# Motor_Control.net
KiCad netlist of a schematic drawn in Altium Designer
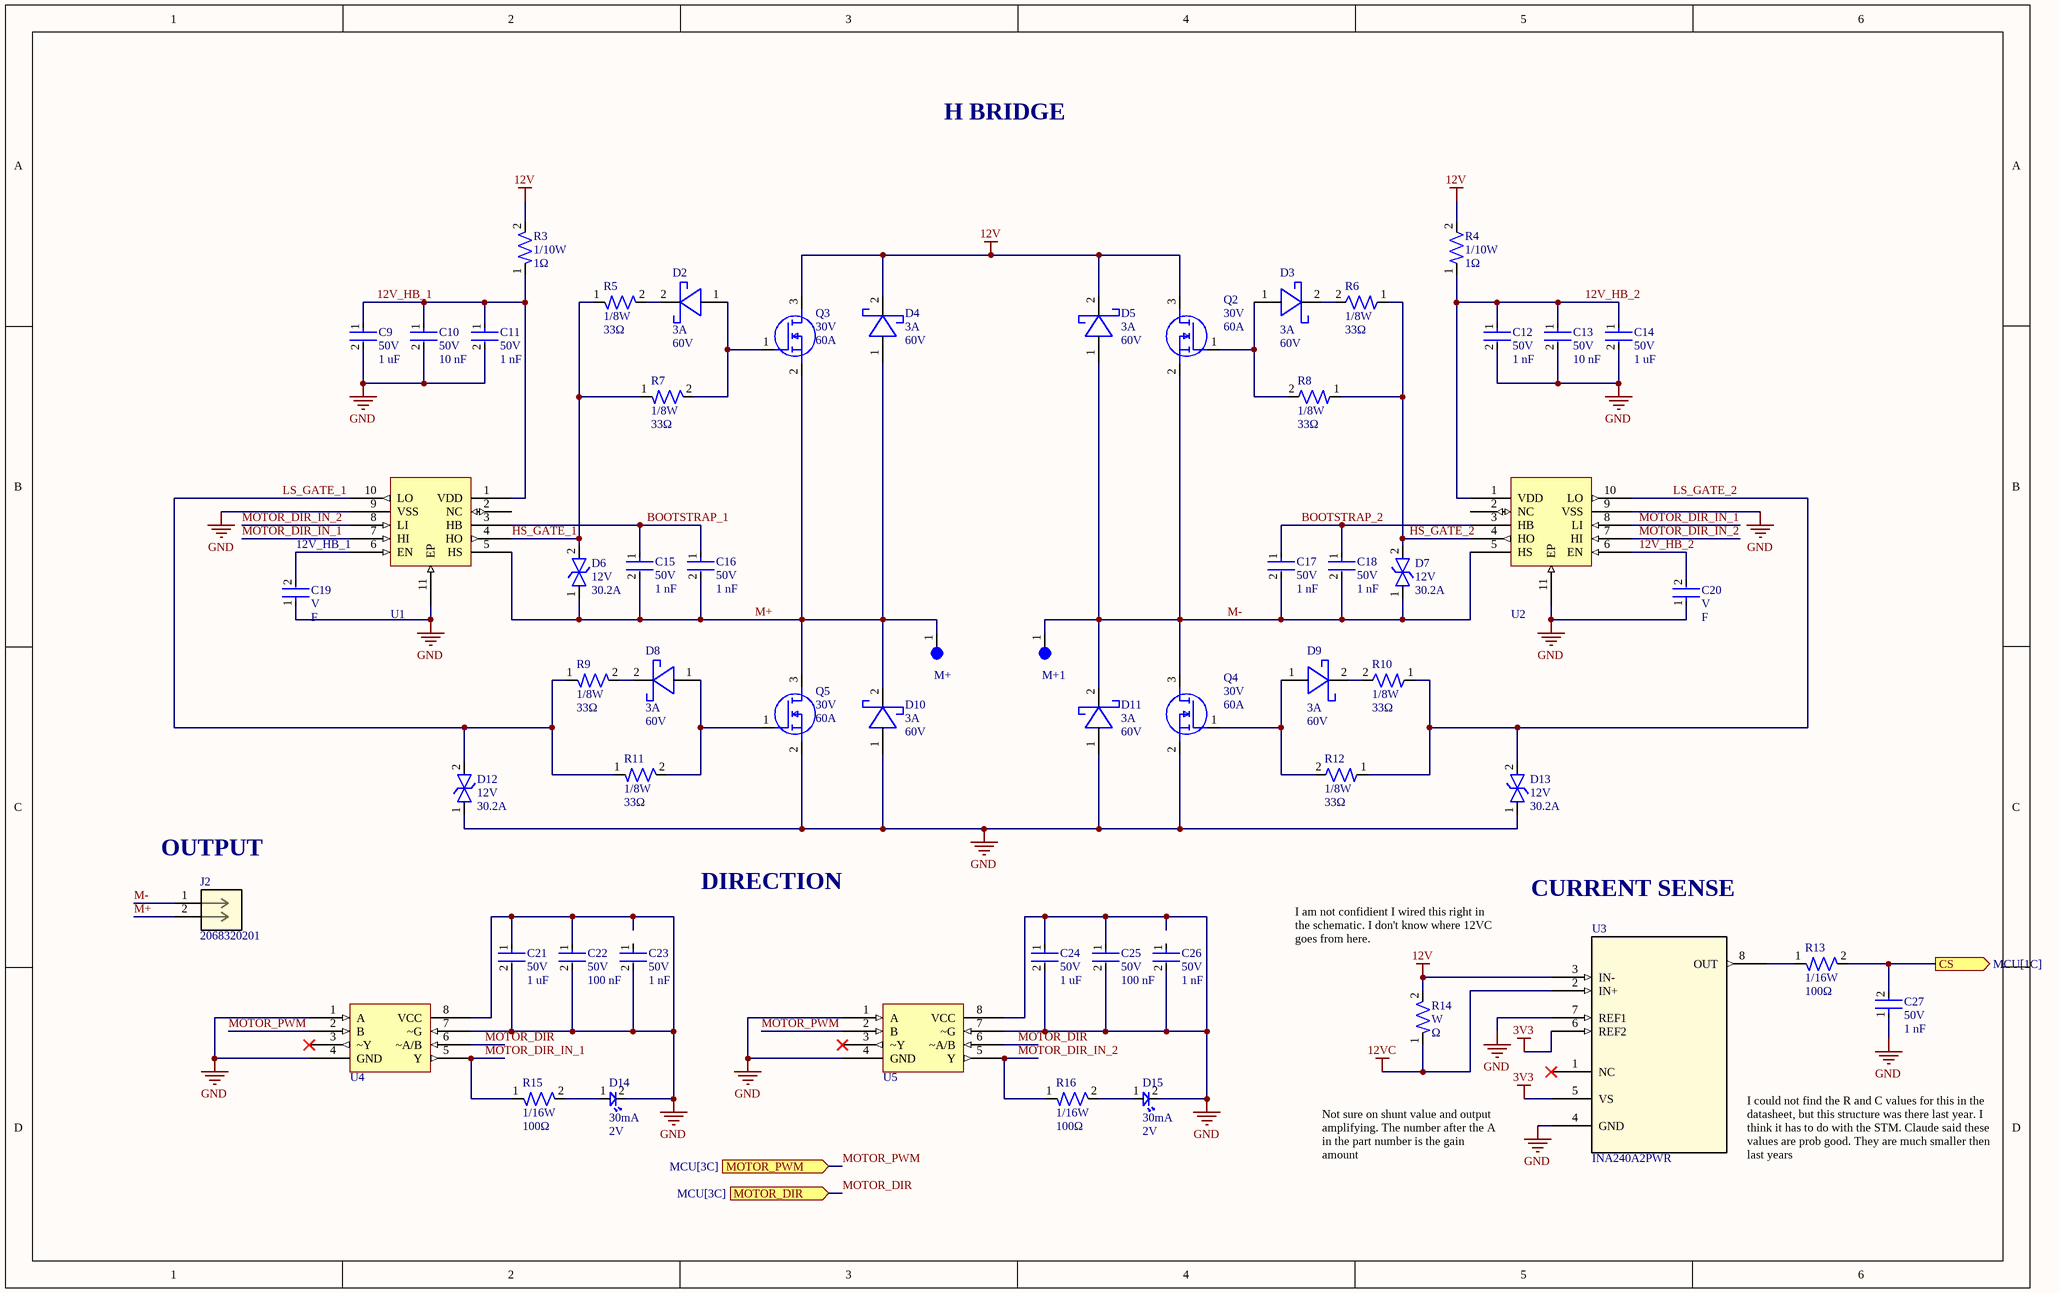
[diagram p0: Motor Control.SchDoc]

(export (version "E")
  (design (tool "Eeschema 10.0.6"))
  (components
    (comp (ref "C9")
      (value "CAP 0805")
      (footprint "CAP-0805")
      (fields (field (name "VOLTAGE RATING") "50V") (field (name "CAPACITANCE") "1 uF"))
      (libsource (lib "EHW_27") (part "CAP 0805"))
    )
    (comp (ref "C10")
      (value "CAP 0805")
      (footprint "CAP-0805")
      (fields (field (name "VOLTAGE RATING") "50V") (field (name "CAPACITANCE") "10 nF"))
      (libsource (lib "EHW_27") (part "CAP 0805"))
    )
    (comp (ref "C11")
      (value "CAP 0805")
      (footprint "CAP-0805")
      (fields (field (name "VOLTAGE RATING") "50V") (field (name "CAPACITANCE") "1 nF"))
      (libsource (lib "EHW_27") (part "CAP 0805"))
    )
    (comp (ref "C12")
      (value "CAP 0805")
      (footprint "CAP-0805")
      (fields (field (name "VOLTAGE RATING") "50V") (field (name "CAPACITANCE") "1 nF"))
      (libsource (lib "EHW_27") (part "CAP 0805"))
    )
    (comp (ref "C13")
      (value "CAP 0805")
      (footprint "CAP-0805")
      (fields (field (name "VOLTAGE RATING") "50V") (field (name "CAPACITANCE") "10 nF"))
      (libsource (lib "EHW_27") (part "CAP 0805"))
    )
    (comp (ref "C14")
      (value "CAP 0805")
      (footprint "CAP-0805")
      (fields (field (name "VOLTAGE RATING") "50V") (field (name "CAPACITANCE") "1 uF"))
      (libsource (lib "EHW_27") (part "CAP 0805"))
    )
    (comp (ref "C15")
      (value "CAP 0805")
      (footprint "CAP-0805")
      (fields (field (name "VOLTAGE RATING") "50V") (field (name "CAPACITANCE") "1 nF"))
      (libsource (lib "EHW_27") (part "CAP 0805"))
    )
    (comp (ref "C16")
      (value "CAP 0805")
      (footprint "CAP-0805")
      (fields (field (name "VOLTAGE RATING") "50V") (field (name "CAPACITANCE") "1 nF"))
      (libsource (lib "EHW_27") (part "CAP 0805"))
    )
    (comp (ref "C17")
      (value "CAP 0805")
      (footprint "CAP-0805")
      (fields (field (name "VOLTAGE RATING") "50V") (field (name "CAPACITANCE") "1 nF"))
      (libsource (lib "EHW_27") (part "CAP 0805"))
    )
    (comp (ref "C18")
      (value "CAP 0805")
      (footprint "CAP-0805")
      (fields (field (name "VOLTAGE RATING") "50V") (field (name "CAPACITANCE") "1 nF"))
      (libsource (lib "EHW_27") (part "CAP 0805"))
    )
    (comp (ref "C19")
      (value "CAP 0603")
      (footprint "CAP-0603")
      (fields (field (name "VOLTAGE RATING") "V") (field (name "CAPACITANCE") "F"))
      (libsource (lib "EHW_27") (part "CAP 0603"))
    )
    (comp (ref "C20")
      (value "CAP 0603")
      (footprint "CAP-0603")
      (fields (field (name "VOLTAGE RATING") "V") (field (name "CAPACITANCE") "F"))
      (libsource (lib "EHW_27") (part "CAP 0603"))
    )
    (comp (ref "C21")
      (value "CAP 0805")
      (footprint "CAP-0805")
      (fields (field (name "VOLTAGE RATING") "50V") (field (name "CAPACITANCE") "1 uF"))
      (libsource (lib "EHW_27") (part "CAP 0805"))
    )
    (comp (ref "C22")
      (value "CAP 0805")
      (footprint "CAP-0805")
      (fields (field (name "VOLTAGE RATING") "50V") (field (name "CAPACITANCE") "100 nF"))
      (libsource (lib "EHW_27") (part "CAP 0805"))
    )
    (comp (ref "C23")
      (value "CAP 0805")
      (footprint "CAP-0805")
      (fields (field (name "VOLTAGE RATING") "50V") (field (name "CAPACITANCE") "1 nF"))
      (libsource (lib "EHW_27") (part "CAP 0805"))
    )
    (comp (ref "C24")
      (value "CAP 0805")
      (footprint "CAP-0805")
      (fields (field (name "VOLTAGE RATING") "50V") (field (name "CAPACITANCE") "1 uF"))
      (libsource (lib "EHW_27") (part "CAP 0805"))
    )
    (comp (ref "C25")
      (value "CAP 0805")
      (footprint "CAP-0805")
      (fields (field (name "VOLTAGE RATING") "50V") (field (name "CAPACITANCE") "100 nF"))
      (libsource (lib "EHW_27") (part "CAP 0805"))
    )
    (comp (ref "C26")
      (value "CAP 0805")
      (footprint "CAP-0805")
      (fields (field (name "VOLTAGE RATING") "50V") (field (name "CAPACITANCE") "1 nF"))
      (libsource (lib "EHW_27") (part "CAP 0805"))
    )
    (comp (ref "C27")
      (value "CAP 0805")
      (footprint "CAP-0805")
      (fields (field (name "VOLTAGE RATING") "50V") (field (name "CAPACITANCE") "1 nF"))
      (libsource (lib "EHW_27") (part "CAP 0805"))
    )
    (comp (ref "D2")
      (value "PMEG6030EP,115")
      (footprint "DIO-SOD128")
      (description "DIODE SCHOTTKY 60V 3A SOD128")
      (fields (field (name "CURRENT RATING") "3A") (field (name "REVERSE VOLTAGE") "60V"))
      (libsource (lib "EHW_27") (part "DIO-SCHOTTKY-0003"))
    )
    (comp (ref "D3")
      (value "PMEG6030EP,115")
      (footprint "DIO-SOD128")
      (description "DIODE SCHOTTKY 60V 3A SOD128")
      (fields (field (name "CURRENT RATING") "3A") (field (name "REVERSE VOLTAGE") "60V"))
      (libsource (lib "EHW_27") (part "DIO-SCHOTTKY-0003"))
    )
    (comp (ref "D4")
      (value "PMEG6030EP,115")
      (footprint "DIO-SOD128")
      (description "DIODE SCHOTTKY 60V 3A SOD128")
      (fields (field (name "CURRENT RATING") "3A") (field (name "REVERSE VOLTAGE") "60V"))
      (libsource (lib "EHW_27") (part "DIO-SCHOTTKY-0003"))
    )
    (comp (ref "D5")
      (value "PMEG6030EP,115")
      (footprint "DIO-SOD128")
      (description "DIODE SCHOTTKY 60V 3A SOD128")
      (fields (field (name "CURRENT RATING") "3A") (field (name "REVERSE VOLTAGE") "60V"))
      (libsource (lib "EHW_27") (part "DIO-SCHOTTKY-0003"))
    )
    (comp (ref "D6")
      (value "SMBJ40CA")
      (footprint "DO-214AA (SMBJ)")
      (description "TVS DIODE 40VWM 64.5VC DO214AA")
      (fields (field (name "VOLTAGE RATING") "12V") (field (name "CURRENT RATING") "30.2A"))
      (libsource (lib "EHW_27") (part "DIO-TVS-0001"))
    )
    (comp (ref "D7")
      (value "SMBJ40CA")
      (footprint "DO-214AA (SMBJ)")
      (description "TVS DIODE 40VWM 64.5VC DO214AA")
      (fields (field (name "VOLTAGE RATING") "12V") (field (name "CURRENT RATING") "30.2A"))
      (libsource (lib "EHW_27") (part "DIO-TVS-0001"))
    )
    (comp (ref "D8")
      (value "PMEG6030EP,115")
      (footprint "DIO-SOD128")
      (description "DIODE SCHOTTKY 60V 3A SOD128")
      (fields (field (name "CURRENT RATING") "3A") (field (name "REVERSE VOLTAGE") "60V"))
      (libsource (lib "EHW_27") (part "DIO-SCHOTTKY-0003"))
    )
    (comp (ref "D9")
      (value "PMEG6030EP,115")
      (footprint "DIO-SOD128")
      (description "DIODE SCHOTTKY 60V 3A SOD128")
      (fields (field (name "CURRENT RATING") "3A") (field (name "REVERSE VOLTAGE") "60V"))
      (libsource (lib "EHW_27") (part "DIO-SCHOTTKY-0003"))
    )
    (comp (ref "D10")
      (value "PMEG6030EP,115")
      (footprint "DIO-SOD128")
      (description "DIODE SCHOTTKY 60V 3A SOD128")
      (fields (field (name "CURRENT RATING") "3A") (field (name "REVERSE VOLTAGE") "60V"))
      (libsource (lib "EHW_27") (part "DIO-SCHOTTKY-0003"))
    )
    (comp (ref "D11")
      (value "PMEG6030EP,115")
      (footprint "DIO-SOD128")
      (description "DIODE SCHOTTKY 60V 3A SOD128")
      (fields (field (name "CURRENT RATING") "3A") (field (name "REVERSE VOLTAGE") "60V"))
      (libsource (lib "EHW_27") (part "DIO-SCHOTTKY-0003"))
    )
    (comp (ref "D12")
      (value "SMBJ40CA")
      (footprint "DO-214AA (SMBJ)")
      (description "TVS DIODE 40VWM 64.5VC DO214AA")
      (fields (field (name "VOLTAGE RATING") "12V") (field (name "CURRENT RATING") "30.2A"))
      (libsource (lib "EHW_27") (part "DIO-TVS-0001"))
    )
    (comp (ref "D13")
      (value "SMBJ40CA")
      (footprint "DO-214AA (SMBJ)")
      (description "TVS DIODE 40VWM 64.5VC DO214AA")
      (fields (field (name "VOLTAGE RATING") "12V") (field (name "CURRENT RATING") "30.2A"))
      (libsource (lib "EHW_27") (part "DIO-TVS-0001"))
    )
    (comp (ref "D14")
      (value "BL-HKC36G-AV-TRB")
      (footprint "LED-0603")
      (description "LED YELLOW CLEAR 0603 SMD")
      (fields (field (name "FORWARD CURRENT") "30mA") (field (name "FORWARD VOLTAGE") "2V"))
      (libsource (lib "EHW_27") (part "LED-0001"))
    )
    (comp (ref "D15")
      (value "BL-HKC36G-AV-TRB")
      (footprint "LED-0603")
      (description "LED YELLOW CLEAR 0603 SMD")
      (fields (field (name "FORWARD CURRENT") "30mA") (field (name "FORWARD VOLTAGE") "2V"))
      (libsource (lib "EHW_27") (part "LED-0001"))
    )
    (comp (ref "J2")
      (value "2068320201")
      (footprint "CONN_2068320000-SD_02_MOL")
      (fields (field (name "COPYRIGHT") "Copyright (C) 2025 Ultra Librarian. All rights reserved."))
      (libsource (lib "EHW_27") (part "CONN MF+ 2 PIN VERT"))
    )
    (comp (ref "M+")
      (value "5003")
      (footprint "TEST-POINT-0001")
      (description "Oranange PC Test Point, Miniature Phoisphor Bronze Silver Plating Through Hole Mounting Type")
      (libsource (lib "EHW_27") (part "TEST-POINT-0001"))
    )
    (comp (ref "M+1")
      (value "5003")
      (footprint "TEST-POINT-0001")
      (description "Oranange PC Test Point, Miniature Phoisphor Bronze Silver Plating Through Hole Mounting Type")
      (libsource (lib "EHW_27") (part "TEST-POINT-0001"))
    )
    (comp (ref "Q2")
      (value "CSD17575Q3")
      (footprint "IC-8VSONCLIP")
      (description "MOSFET N-CH 30V 60A 8VSON")
      (fields (field (name "VOLTAGE") "30V") (field (name "CONTINUOUS CURRENT") "60A"))
      (libsource (lib "EHW_27") (part "NMOS-26A-0001"))
    )
    (comp (ref "Q3")
      (value "CSD17575Q3")
      (footprint "IC-8VSONCLIP")
      (description "MOSFET N-CH 30V 60A 8VSON")
      (fields (field (name "VOLTAGE") "30V") (field (name "CONTINUOUS CURRENT") "60A"))
      (libsource (lib "EHW_27") (part "NMOS-26A-0001"))
    )
    (comp (ref "Q4")
      (value "CSD17575Q3")
      (footprint "IC-8VSONCLIP")
      (description "MOSFET N-CH 30V 60A 8VSON")
      (fields (field (name "VOLTAGE") "30V") (field (name "CONTINUOUS CURRENT") "60A"))
      (libsource (lib "EHW_27") (part "NMOS-26A-0001"))
    )
    (comp (ref "Q5")
      (value "CSD17575Q3")
      (footprint "IC-8VSONCLIP")
      (description "MOSFET N-CH 30V 60A 8VSON")
      (fields (field (name "VOLTAGE") "30V") (field (name "CONTINUOUS CURRENT") "60A"))
      (libsource (lib "EHW_27") (part "NMOS-26A-0001"))
    )
    (comp (ref "R3")
      (value "RES 0805")
      (footprint "RES-0805")
      (fields (field (name "WATTAGE") "1/10W") (field (name "RESISTANCE") "1Ω"))
      (libsource (lib "EHW_27") (part "RES 0805"))
    )
    (comp (ref "R4")
      (value "RES 0805")
      (footprint "RES-0805")
      (fields (field (name "WATTAGE") "1/10W") (field (name "RESISTANCE") "1Ω"))
      (libsource (lib "EHW_27") (part "RES 0805"))
    )
    (comp (ref "R5")
      (value "RES 0805")
      (footprint "RES-0805")
      (fields (field (name "WATTAGE") "1/8W") (field (name "RESISTANCE") "33Ω"))
      (libsource (lib "EHW_27") (part "RES 0805"))
    )
    (comp (ref "R6")
      (value "RES 0805")
      (footprint "RES-0805")
      (fields (field (name "WATTAGE") "1/8W") (field (name "RESISTANCE") "33Ω"))
      (libsource (lib "EHW_27") (part "RES 0805"))
    )
    (comp (ref "R7")
      (value "RES 0805")
      (footprint "RES-0805")
      (fields (field (name "WATTAGE") "1/8W") (field (name "RESISTANCE") "33Ω"))
      (libsource (lib "EHW_27") (part "RES 0805"))
    )
    (comp (ref "R8")
      (value "RES 0805")
      (footprint "RES-0805")
      (fields (field (name "WATTAGE") "1/8W") (field (name "RESISTANCE") "33Ω"))
      (libsource (lib "EHW_27") (part "RES 0805"))
    )
    (comp (ref "R9")
      (value "RES 0805")
      (footprint "RES-0805")
      (fields (field (name "WATTAGE") "1/8W") (field (name "RESISTANCE") "33Ω"))
      (libsource (lib "EHW_27") (part "RES 0805"))
    )
    (comp (ref "R10")
      (value "RES 0805")
      (footprint "RES-0805")
      (fields (field (name "WATTAGE") "1/8W") (field (name "RESISTANCE") "33Ω"))
      (libsource (lib "EHW_27") (part "RES 0805"))
    )
    (comp (ref "R11")
      (value "RES 0805")
      (footprint "RES-0805")
      (fields (field (name "WATTAGE") "1/8W") (field (name "RESISTANCE") "33Ω"))
      (libsource (lib "EHW_27") (part "RES 0805"))
    )
    (comp (ref "R12")
      (value "RES 0805")
      (footprint "RES-0805")
      (fields (field (name "WATTAGE") "1/8W") (field (name "RESISTANCE") "33Ω"))
      (libsource (lib "EHW_27") (part "RES 0805"))
    )
    (comp (ref "R13")
      (value "RES 0805")
      (footprint "RES-0805")
      (fields (field (name "WATTAGE") "1/16W") (field (name "RESISTANCE") "100Ω"))
      (libsource (lib "EHW_27") (part "RES 0805"))
    )
    (comp (ref "R14")
      (value "RES 2512")
      (footprint "RES-2512")
      (fields (field (name "WATTAGE") "W") (field (name "RESISTANCE") "Ω"))
      (libsource (lib "EHW_27") (part "RES 2512"))
    )
    (comp (ref "R15")
      (value "RES 0805")
      (footprint "RES-0805")
      (fields (field (name "WATTAGE") "1/16W") (field (name "RESISTANCE") "100Ω"))
      (libsource (lib "EHW_27") (part "RES 0805"))
    )
    (comp (ref "R16")
      (value "RES 0805")
      (footprint "RES-0805")
      (fields (field (name "WATTAGE") "1/16W") (field (name "RESISTANCE") "100Ω"))
      (libsource (lib "EHW_27") (part "RES 0805"))
    )
    (comp (ref "U1")
      (value "UCC27282DRCR")
      (footprint "IC-10VSON")
      (description "IC GATE DRVR HALF-BRIDGE 10VSON")
      (libsource (lib "") (part "IC-GTDR-0001_1"))
    )
    (comp (ref "U2")
      (value "UCC27282DRCR")
      (footprint "IC-10VSON")
      (description "IC GATE DRVR HALF-BRIDGE 10VSON")
      (libsource (lib "EHW_27") (part "IC-GTDR-0001"))
    )
    (comp (ref "U3")
      (value "INA240A2PWR")
      (footprint "PW0008A_N_TEX")
      (fields (field (name "COPYRIGHT") "Copyright (C) 2026 Ultra Librarian. All rights reserved."))
      (libsource (lib "EHW_27") (part "INA240A2PWR"))
    )
    (comp (ref "U4")
      (value "SN74LVC2G157DCUR")
      (footprint "IC-8VSSOP")
      (description "Multiplexer 1 x 2:1 8-VSSOP")
      (libsource (lib "EHW_27") (part "IC-MUX-0001"))
    )
    (comp (ref "U5")
      (value "SN74LVC2G157DCUR")
      (footprint "IC-8VSSOP")
      (description "Multiplexer 1 x 2:1 8-VSSOP")
      (libsource (lib "EHW_27") (part "IC-MUX-0001"))
    )
  )
  (nets
    (net (code "1") (name "/12V_HB_1") (class "Default")
      (node (ref "C10") (pin "1") (pinfunction "1_1") (pintype "passive"))
      (node (ref "C11") (pin "1") (pinfunction "1_1") (pintype "passive"))
      (node (ref "C9") (pin "1") (pinfunction "1_1") (pintype "passive"))
      (node (ref "R3") (pin "1") (pinfunction "1_1") (pintype "passive"))
      (node (ref "U1") (pin "1") (pinfunction "VDD_1") (pintype "power_in"))
    )
    (net (code "2") (name "/12V_HB_2") (class "Default")
      (node (ref "C12") (pin "1") (pinfunction "1_1") (pintype "passive"))
      (node (ref "C13") (pin "1") (pinfunction "1_1") (pintype "passive"))
      (node (ref "C14") (pin "1") (pinfunction "1_1") (pintype "passive"))
      (node (ref "C20") (pin "2") (pinfunction "2_2") (pintype "passive"))
      (node (ref "R4") (pin "1") (pinfunction "1_1") (pintype "passive"))
      (node (ref "U2") (pin "1") (pinfunction "VDD_1") (pintype "power_in"))
      (node (ref "U2") (pin "6") (pinfunction "EN_6") (pintype "input"))
    )
    (net (code "3") (name "/BOOTSTRAP_1") (class "Default")
      (node (ref "C15") (pin "1") (pinfunction "1_1") (pintype "passive"))
      (node (ref "C16") (pin "1") (pinfunction "1_1") (pintype "passive"))
      (node (ref "U1") (pin "3") (pinfunction "HB_3") (pintype "power_in"))
    )
    (net (code "4") (name "/BOOTSTRAP_2") (class "Default")
      (node (ref "C17") (pin "1") (pinfunction "1_1") (pintype "passive"))
      (node (ref "C18") (pin "1") (pinfunction "1_1") (pintype "passive"))
      (node (ref "U2") (pin "3") (pinfunction "HB_3") (pintype "power_in"))
    )
    (net (code "5") (name "/CS") (class "Default")
      (node (ref "C27") (pin "2") (pinfunction "2_2") (pintype "passive"))
      (node (ref "R13") (pin "2") (pinfunction "2_2") (pintype "passive"))
    )
    (net (code "6") (name "/HS_GATE_1") (class "Default")
      (node (ref "D6") (pin "2") (pintype "passive"))
      (node (ref "R5") (pin "1") (pinfunction "1_1") (pintype "passive"))
      (node (ref "R7") (pin "1") (pinfunction "1_1") (pintype "passive"))
      (node (ref "U1") (pin "4") (pinfunction "HO_4") (pintype "output"))
    )
    (net (code "7") (name "/HS_GATE_2") (class "Default")
      (node (ref "D7") (pin "2") (pintype "passive"))
      (node (ref "R6") (pin "1") (pinfunction "1_1") (pintype "passive"))
      (node (ref "R8") (pin "1") (pinfunction "1_1") (pintype "passive"))
      (node (ref "U2") (pin "4") (pinfunction "HO_4") (pintype "output"))
    )
    (net (code "8") (name "/LS_GATE_1") (class "Default")
      (node (ref "D12") (pin "2") (pintype "passive"))
      (node (ref "R11") (pin "1") (pinfunction "1_1") (pintype "passive"))
      (node (ref "R9") (pin "1") (pinfunction "1_1") (pintype "passive"))
      (node (ref "U1") (pin "10") (pinfunction "LO_10") (pintype "output"))
    )
    (net (code "9") (name "/LS_GATE_2") (class "Default")
      (node (ref "D13") (pin "2") (pintype "passive"))
      (node (ref "R10") (pin "1") (pinfunction "1_1") (pintype "passive"))
      (node (ref "R12") (pin "1") (pinfunction "1_1") (pintype "passive"))
      (node (ref "U2") (pin "10") (pinfunction "LO_10") (pintype "output"))
    )
    (net (code "10") (name "/M+") (class "Default")
      (node (ref "C15") (pin "2") (pinfunction "2_2") (pintype "passive"))
      (node (ref "C16") (pin "2") (pinfunction "2_2") (pintype "passive"))
      (node (ref "D10") (pin "2") (pinfunction "ANODE_2") (pintype "passive"))
      (node (ref "D4") (pin "1") (pinfunction "CATHODE_1") (pintype "passive"))
      (node (ref "D6") (pin "1") (pintype "passive"))
      (node (ref "J2") (pin "2") (pinfunction "2_2") (pintype "passive"))
      (node (ref "M+") (pin "1") (pinfunction "0_1") (pintype "passive"))
      (node (ref "Q3") (pin "2") (pinfunction "S_2") (pintype "passive"))
      (node (ref "Q5") (pin "3") (pinfunction "D_3") (pintype "passive"))
      (node (ref "U1") (pin "5") (pinfunction "HS_5") (pintype "power_in"))
    )
    (net (code "11") (name "/M-") (class "Default")
      (node (ref "C17") (pin "2") (pinfunction "2_2") (pintype "passive"))
      (node (ref "C18") (pin "2") (pinfunction "2_2") (pintype "passive"))
      (node (ref "D11") (pin "2") (pinfunction "ANODE_2") (pintype "passive"))
      (node (ref "D5") (pin "1") (pinfunction "CATHODE_1") (pintype "passive"))
      (node (ref "D7") (pin "1") (pintype "passive"))
      (node (ref "J2") (pin "1") (pinfunction "1_1") (pintype "passive"))
      (node (ref "M+1") (pin "1") (pinfunction "0_1") (pintype "passive"))
      (node (ref "Q2") (pin "2") (pinfunction "S_2") (pintype "passive"))
      (node (ref "Q4") (pin "3") (pinfunction "D_3") (pintype "passive"))
      (node (ref "U2") (pin "5") (pinfunction "HS_5") (pintype "power_in"))
    )
    (net (code "12") (name "/MOTOR_DIR") (class "Default")
      (node (ref "U4") (pin "6") (pinfunction "~A/B_6") (pintype "input"))
      (node (ref "U5") (pin "6") (pinfunction "~A/B_6") (pintype "input"))
    )
    (net (code "13") (name "/MOTOR_DIR_IN_1") (class "Default")
      (node (ref "R15") (pin "1") (pinfunction "1_1") (pintype "passive"))
      (node (ref "U1") (pin "7") (pinfunction "HI_7") (pintype "input"))
      (node (ref "U2") (pin "8") (pinfunction "LI_8") (pintype "input"))
      (node (ref "U4") (pin "5") (pinfunction "Y_5") (pintype "output"))
    )
    (net (code "14") (name "/MOTOR_DIR_IN_2") (class "Default")
      (node (ref "R16") (pin "1") (pinfunction "1_1") (pintype "passive"))
      (node (ref "U1") (pin "8") (pinfunction "LI_8") (pintype "input"))
      (node (ref "U2") (pin "7") (pinfunction "HI_7") (pintype "input"))
      (node (ref "U5") (pin "5") (pinfunction "Y_5") (pintype "output"))
    )
    (net (code "15") (name "/MOTOR_PWM") (class "Default")
      (node (ref "U4") (pin "2") (pinfunction "B_2") (pintype "input"))
      (node (ref "U5") (pin "2") (pinfunction "B_2") (pintype "input"))
    )
    (net (code "16") (name "3V3") (class "Default")
      (node (ref "U3") (pin "5") (pinfunction "VS_5") (pintype "power_in"))
      (node (ref "U3") (pin "6") (pinfunction "REF2_6") (pintype "input"))
    )
    (net (code "17") (name "12V") (class "Default")
      (node (ref "D4") (pin "2") (pinfunction "ANODE_2") (pintype "passive"))
      (node (ref "D5") (pin "2") (pinfunction "ANODE_2") (pintype "passive"))
      (node (ref "Q2") (pin "3") (pinfunction "D_3") (pintype "passive"))
      (node (ref "Q3") (pin "3") (pinfunction "D_3") (pintype "passive"))
      (node (ref "R14") (pin "2") (pinfunction "2_2") (pintype "passive"))
      (node (ref "R3") (pin "2") (pinfunction "2_2") (pintype "passive"))
      (node (ref "R4") (pin "2") (pinfunction "2_2") (pintype "passive"))
      (node (ref "U3") (pin "3") (pinfunction "IN-_3") (pintype "input"))
    )
    (net (code "18") (name "12VC") (class "Default")
      (node (ref "R14") (pin "1") (pinfunction "1_1") (pintype "passive"))
      (node (ref "U3") (pin "2") (pinfunction "IN+_2") (pintype "input"))
    )
    (net (code "19") (name "GND") (class "Default")
      (node (ref "C10") (pin "2") (pinfunction "2_2") (pintype "passive"))
      (node (ref "C11") (pin "2") (pinfunction "2_2") (pintype "passive"))
      (node (ref "C12") (pin "2") (pinfunction "2_2") (pintype "passive"))
      (node (ref "C13") (pin "2") (pinfunction "2_2") (pintype "passive"))
      (node (ref "C14") (pin "2") (pinfunction "2_2") (pintype "passive"))
      (node (ref "C19") (pin "1") (pinfunction "1_1") (pintype "passive"))
      (node (ref "C20") (pin "1") (pinfunction "1_1") (pintype "passive"))
      (node (ref "C21") (pin "1") (pinfunction "1_1") (pintype "passive"))
      (node (ref "C21") (pin "2") (pinfunction "2_2") (pintype "passive"))
      (node (ref "C22") (pin "1") (pinfunction "1_1") (pintype "passive"))
      (node (ref "C22") (pin "2") (pinfunction "2_2") (pintype "passive"))
      (node (ref "C23") (pin "2") (pinfunction "2_2") (pintype "passive"))
      (node (ref "C24") (pin "1") (pinfunction "1_1") (pintype "passive"))
      (node (ref "C24") (pin "2") (pinfunction "2_2") (pintype "passive"))
      (node (ref "C25") (pin "1") (pinfunction "1_1") (pintype "passive"))
      (node (ref "C25") (pin "2") (pinfunction "2_2") (pintype "passive"))
      (node (ref "C26") (pin "2") (pinfunction "2_2") (pintype "passive"))
      (node (ref "C27") (pin "1") (pinfunction "1_1") (pintype "passive"))
      (node (ref "C9") (pin "2") (pinfunction "2_2") (pintype "passive"))
      (node (ref "D10") (pin "1") (pinfunction "CATHODE_1") (pintype "passive"))
      (node (ref "D11") (pin "1") (pinfunction "CATHODE_1") (pintype "passive"))
      (node (ref "D12") (pin "1") (pintype "passive"))
      (node (ref "D13") (pin "1") (pintype "passive"))
      (node (ref "D14") (pin "2") (pinfunction "2_2") (pintype "passive"))
      (node (ref "D15") (pin "2") (pinfunction "2_2") (pintype "passive"))
      (node (ref "Q4") (pin "2") (pinfunction "S_2") (pintype "passive"))
      (node (ref "Q5") (pin "2") (pinfunction "S_2") (pintype "passive"))
      (node (ref "U1") (pin "11") (pinfunction "EP_11") (pintype "input"))
      (node (ref "U1") (pin "9") (pinfunction "VSS_9") (pintype "power_in"))
      (node (ref "U2") (pin "11") (pinfunction "EP_11") (pintype "input"))
      (node (ref "U2") (pin "9") (pinfunction "VSS_9") (pintype "power_in"))
      (node (ref "U3") (pin "4") (pinfunction "GND_4") (pintype "power_in"))
      (node (ref "U3") (pin "7") (pinfunction "REF1_7") (pintype "input"))
      (node (ref "U4") (pin "1") (pinfunction "A_1") (pintype "input"))
      (node (ref "U4") (pin "4") (pinfunction "GND_4") (pintype "power_in"))
      (node (ref "U4") (pin "7") (pinfunction "~G_7") (pintype "input"))
      (node (ref "U4") (pin "8") (pinfunction "VCC_8") (pintype "power_in"))
      (node (ref "U5") (pin "1") (pinfunction "A_1") (pintype "input"))
      (node (ref "U5") (pin "4") (pinfunction "GND_4") (pintype "power_in"))
      (node (ref "U5") (pin "7") (pinfunction "~G_7") (pintype "input"))
      (node (ref "U5") (pin "8") (pinfunction "VCC_8") (pintype "power_in"))
    )
    (net (code "20") (name "Net-(D2-ANODE)") (class "Default")
      (node (ref "D2") (pin "2") (pinfunction "ANODE_2") (pintype "passive"))
      (node (ref "R5") (pin "2") (pinfunction "2_2") (pintype "passive"))
    )
    (net (code "21") (name "Net-(D2-CATHODE)") (class "Default")
      (node (ref "D2") (pin "1") (pinfunction "CATHODE_1") (pintype "passive"))
      (node (ref "Q3") (pin "1") (pinfunction "G_1") (pintype "passive"))
      (node (ref "R7") (pin "2") (pinfunction "2_2") (pintype "passive"))
    )
    (net (code "22") (name "Net-(D3-ANODE)") (class "Default")
      (node (ref "D3") (pin "2") (pinfunction "ANODE_2") (pintype "passive"))
      (node (ref "R6") (pin "2") (pinfunction "2_2") (pintype "passive"))
    )
    (net (code "23") (name "Net-(D3-CATHODE)") (class "Default")
      (node (ref "D3") (pin "1") (pinfunction "CATHODE_1") (pintype "passive"))
      (node (ref "Q2") (pin "1") (pinfunction "G_1") (pintype "passive"))
      (node (ref "R8") (pin "2") (pinfunction "2_2") (pintype "passive"))
    )
    (net (code "24") (name "Net-(D8-ANODE)") (class "Default")
      (node (ref "D8") (pin "2") (pinfunction "ANODE_2") (pintype "passive"))
      (node (ref "R9") (pin "2") (pinfunction "2_2") (pintype "passive"))
    )
    (net (code "25") (name "Net-(D8-CATHODE)") (class "Default")
      (node (ref "D8") (pin "1") (pinfunction "CATHODE_1") (pintype "passive"))
      (node (ref "Q5") (pin "1") (pinfunction "G_1") (pintype "passive"))
      (node (ref "R11") (pin "2") (pinfunction "2_2") (pintype "passive"))
    )
    (net (code "26") (name "Net-(D9-ANODE)") (class "Default")
      (node (ref "D9") (pin "2") (pinfunction "ANODE_2") (pintype "passive"))
      (node (ref "R10") (pin "2") (pinfunction "2_2") (pintype "passive"))
    )
    (net (code "27") (name "Net-(D9-CATHODE)") (class "Default")
      (node (ref "D9") (pin "1") (pinfunction "CATHODE_1") (pintype "passive"))
      (node (ref "Q4") (pin "1") (pinfunction "G_1") (pintype "passive"))
      (node (ref "R12") (pin "2") (pinfunction "2_2") (pintype "passive"))
    )
    (net (code "28") (name "Net-(D14-Pad1)") (class "Default")
      (node (ref "D14") (pin "1") (pinfunction "1_1") (pintype "passive"))
      (node (ref "R15") (pin "2") (pinfunction "2_2") (pintype "passive"))
    )
    (net (code "29") (name "Net-(D15-Pad1)") (class "Default")
      (node (ref "D15") (pin "1") (pinfunction "1_1") (pintype "passive"))
      (node (ref "R16") (pin "2") (pinfunction "2_2") (pintype "passive"))
    )
    (net (code "30") (name "Net-(U1-EN)") (class "Default")
      (node (ref "C19") (pin "2") (pinfunction "2_2") (pintype "passive"))
      (node (ref "U1") (pin "6") (pinfunction "EN_6") (pintype "input"))
    )
    (net (code "31") (name "Net-(U3-OUT)") (class "Default")
      (node (ref "R13") (pin "1") (pinfunction "1_1") (pintype "passive"))
      (node (ref "U3") (pin "8") (pinfunction "OUT_8") (pintype "output"))
    )
    (net (code "32") (name "unconnected-(C23-Pad1)") (class "Default")
      (node (ref "C23") (pin "1") (pinfunction "1_1") (pintype "passive"))
    )
    (net (code "33") (name "unconnected-(C26-Pad1)") (class "Default")
      (node (ref "C26") (pin "1") (pinfunction "1_1") (pintype "passive"))
    )
    (net (code "34") (name "unconnected-(U1-NC-Pad2)") (class "Default")
      (node (ref "U1") (pin "2") (pinfunction "NC_2") (pintype "bidirectional"))
    )
    (net (code "35") (name "unconnected-(U2-NC-Pad2)") (class "Default")
      (node (ref "U2") (pin "2") (pinfunction "NC_2") (pintype "bidirectional"))
    )
    (net (code "36") (name "unconnected-(U3-NC-Pad1)") (class "Default")
      (node (ref "U3") (pin "1") (pinfunction "NC_1") (pintype "passive+no_connect"))
    )
    (net (code "37") (name "unconnected-(U4-~Y-Pad3)") (class "Default")
      (node (ref "U4") (pin "3") (pinfunction "~Y_3") (pintype "output+no_connect"))
    )
    (net (code "38") (name "unconnected-(U5-~Y-Pad3)") (class "Default")
      (node (ref "U5") (pin "3") (pinfunction "~Y_3") (pintype "output+no_connect"))
    )
  )
)
